# Pit_Crew.net
KiCad netlist of a schematic drawn in EAGLE
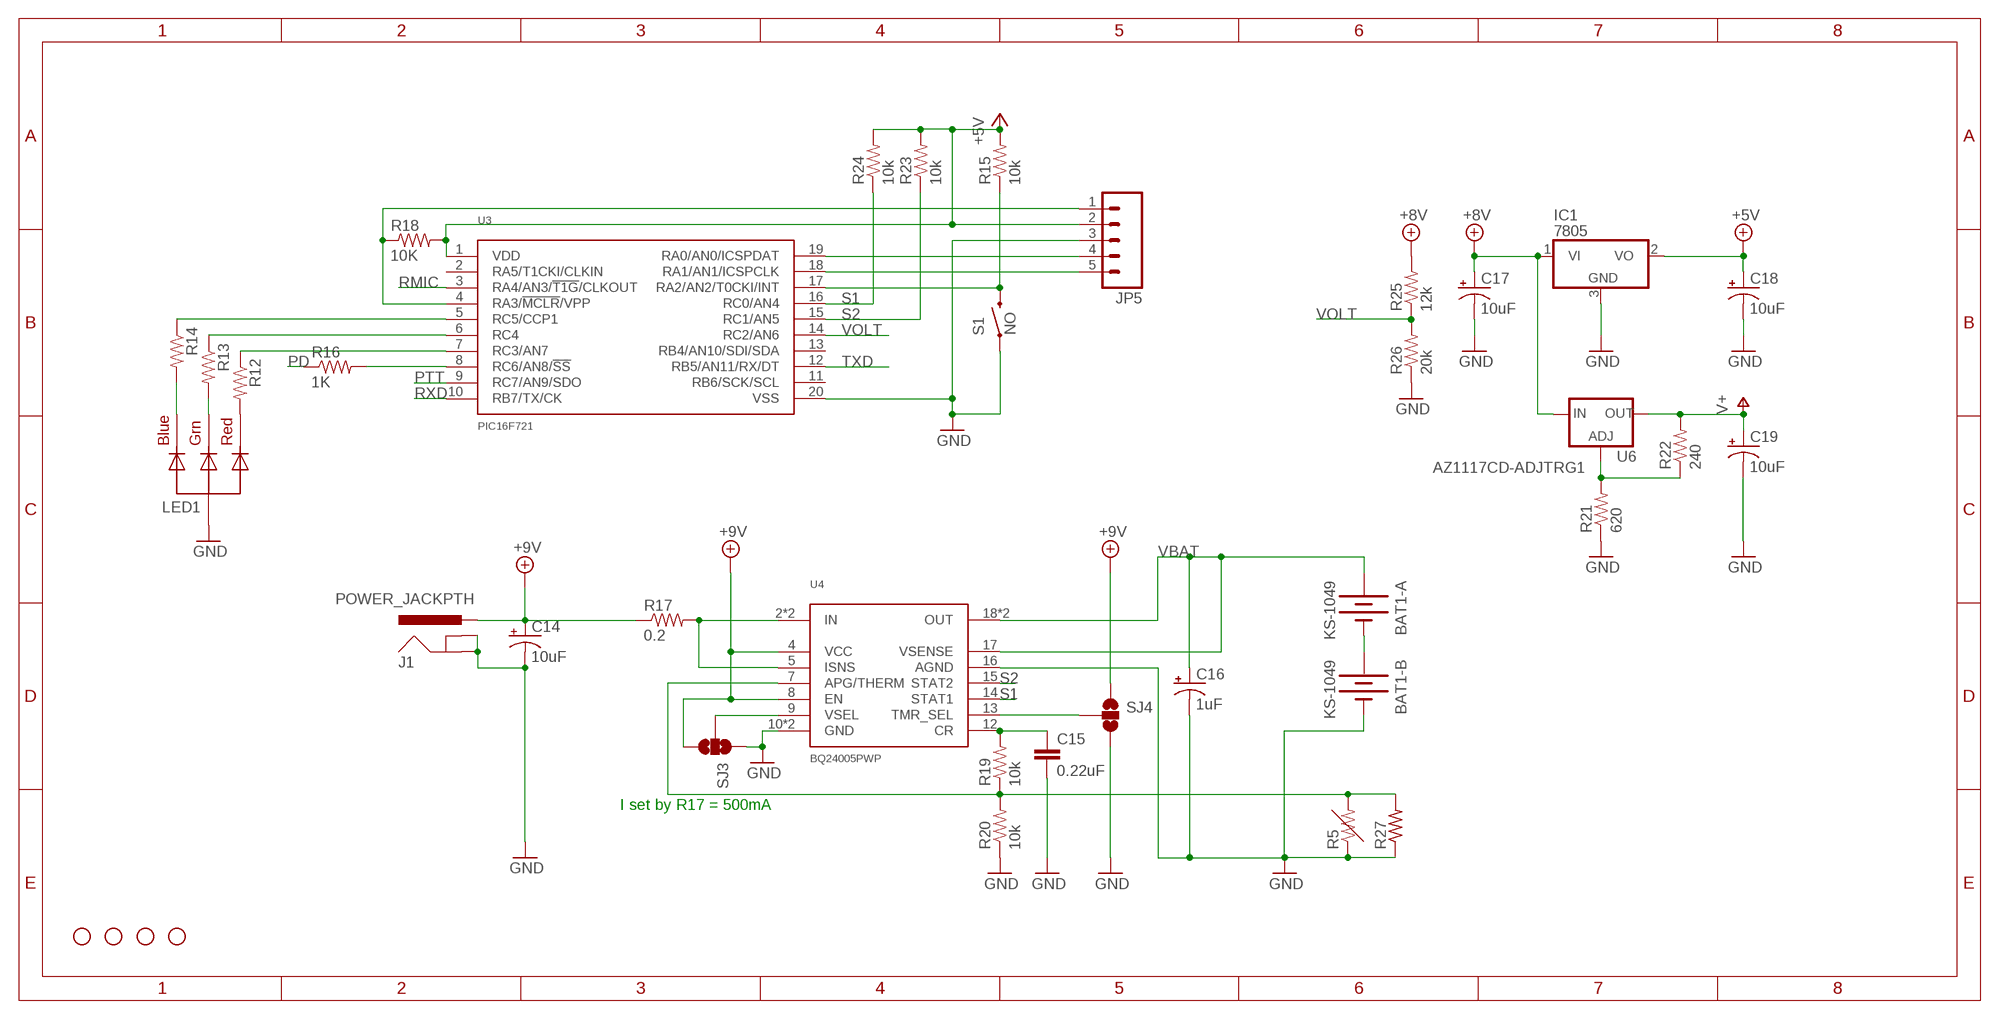
[diagram p0: schematic, sheet 1]
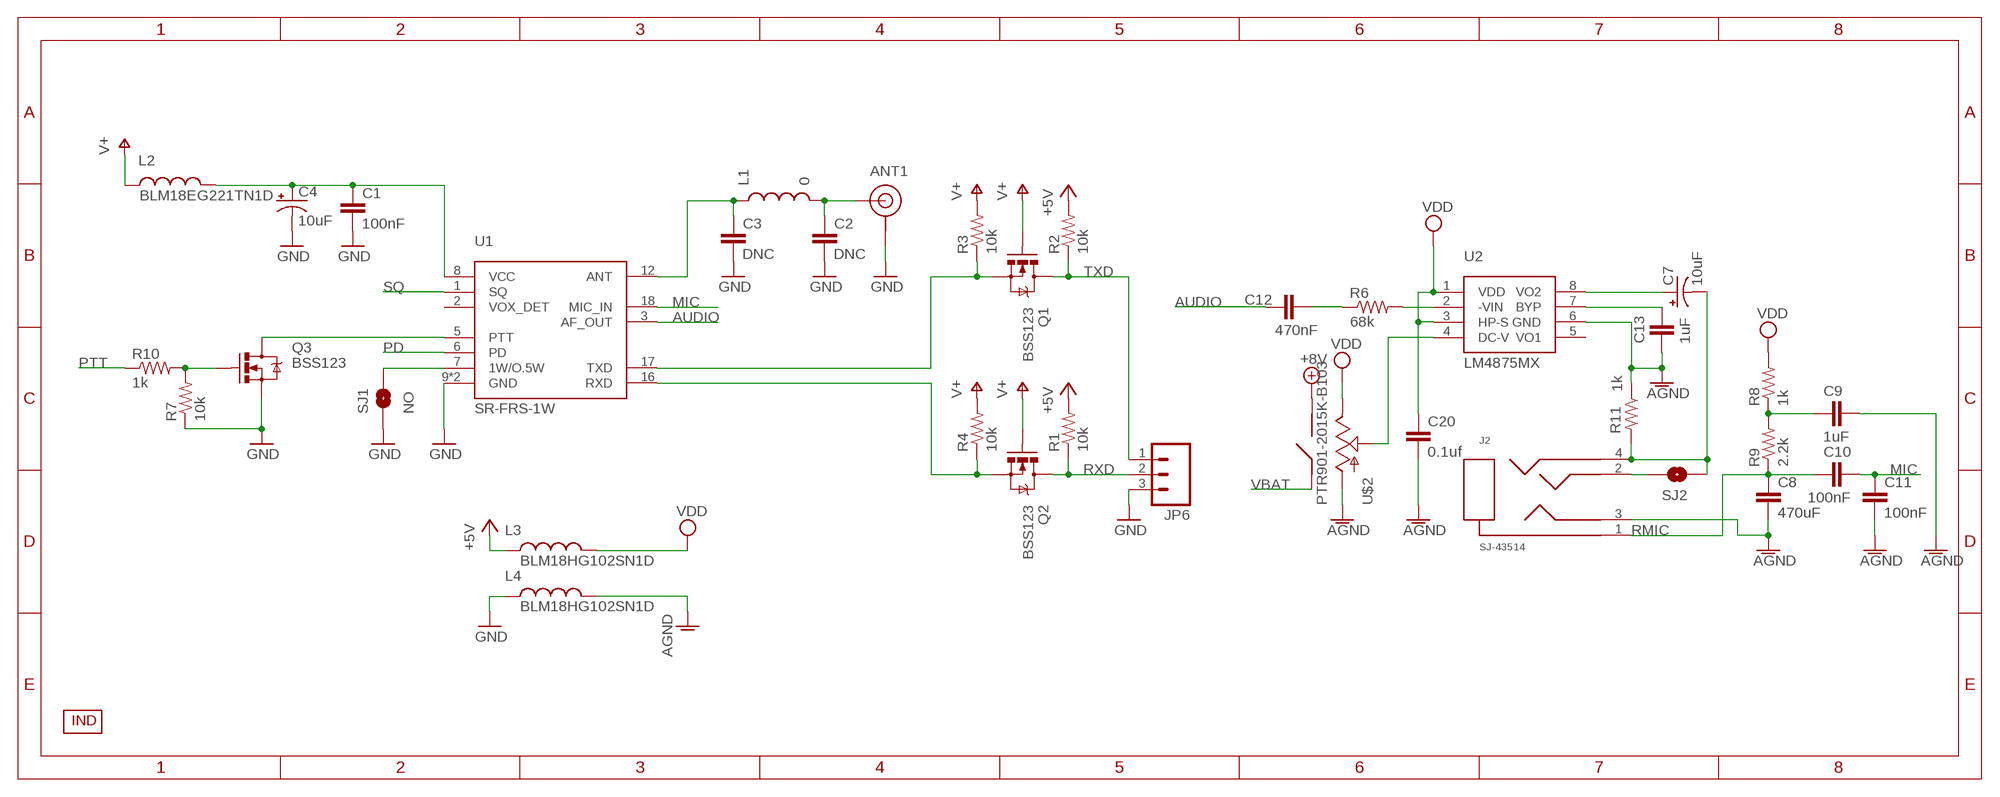
[diagram p1: schematic, sheet 2]

(export (version "E")
  (design (tool "Eeschema 10.0.6"))
  (components
    (comp (ref "ANT1")
      (value "SMA")
      (footprint "eagle-import:CONSMA002")
      (libsource (lib "eagle-import") (part "SMA"))
    )
    (comp (ref "C1")
      (value "100nF")
      (footprint "eagle-import:0805")
      (libsource (lib "eagle-import") (part "CAP0805"))
    )
    (comp (ref "C2")
      (value "DNC")
      (footprint "eagle-import:0805")
      (libsource (lib "eagle-import") (part "CAP0805"))
    )
    (comp (ref "C3")
      (value "DNC")
      (footprint "eagle-import:0805")
      (libsource (lib "eagle-import") (part "CAP0805"))
    )
    (comp (ref "C4")
      (value "10uF")
      (footprint "eagle-import:EIA3216")
      (libsource (lib "eagle-import") (part "CAP_POL1206"))
    )
    (comp (ref "C7")
      (value "10uF")
      (footprint "eagle-import:EIA3216")
      (libsource (lib "eagle-import") (part "10UF-TANT"))
    )
    (comp (ref "C8")
      (value "470uF")
      (footprint "eagle-import:0805")
      (libsource (lib "eagle-import") (part "CAP0805"))
    )
    (comp (ref "C9")
      (value "1uF")
      (footprint "eagle-import:0805")
      (libsource (lib "eagle-import") (part "CAP0805"))
    )
    (comp (ref "C10")
      (value "100nF")
      (footprint "eagle-import:0805")
      (libsource (lib "eagle-import") (part "CAP0805"))
    )
    (comp (ref "C11")
      (value "100nF")
      (footprint "eagle-import:0805")
      (libsource (lib "eagle-import") (part "CAP0805"))
    )
    (comp (ref "C12")
      (value "470nF")
      (footprint "eagle-import:0805")
      (libsource (lib "eagle-import") (part "CAP0805"))
    )
    (comp (ref "C13")
      (value "1uF")
      (footprint "eagle-import:0805")
      (libsource (lib "eagle-import") (part "CAP0805"))
    )
    (comp (ref "C20")
      (value "0.1uf")
      (footprint "eagle-import:0805")
      (libsource (lib "eagle-import") (part "CAP0805"))
    )
    (comp (ref "J2")
      (value "SJ-43514")
      (footprint "eagle-import:SJ-43514")
      (libsource (lib "eagle-import") (part "SJ-43514"))
    )
    (comp (ref "JP6")
      (value "M03LOCK")
      (footprint "eagle-import:1X03_LOCK")
      (libsource (lib "eagle-import") (part "M03LOCK"))
    )
    (comp (ref "L1")
      (value "0")
      (footprint "eagle-import:1007")
      (libsource (lib "eagle-import") (part "INDUCTOR1007"))
    )
    (comp (ref "L2")
      (value "BLM18EG221TN1D")
      (footprint "eagle-import:0603")
      (libsource (lib "eagle-import") (part "INDUCTOR0603"))
    )
    (comp (ref "L3")
      (value "BLM18HG102SN1D")
      (footprint "eagle-import:0603")
      (libsource (lib "eagle-import") (part "INDUCTOR0603"))
    )
    (comp (ref "L4")
      (value "BLM18HG102SN1D")
      (footprint "eagle-import:0603")
      (libsource (lib "eagle-import") (part "INDUCTOR0603"))
    )
    (comp (ref "Q1")
      (value "BSS123")
      (footprint "eagle-import:SOT23")
      (libsource (lib "eagle-import") (part "MOSFET-NCHANNELBSS123LT1G"))
    )
    (comp (ref "Q2")
      (value "BSS123")
      (footprint "eagle-import:SOT23")
      (libsource (lib "eagle-import") (part "MOSFET-NCHANNELBSS123LT1G"))
    )
    (comp (ref "Q3")
      (value "BSS123")
      (footprint "eagle-import:SOT23")
      (libsource (lib "eagle-import") (part "MOSFET-NCHANNELBSS123LT1G"))
    )
    (comp (ref "R1")
      (value "10k")
      (footprint "eagle-import:0805")
      (libsource (lib "eagle-import") (part "RESISTOR0805-RES"))
    )
    (comp (ref "R2")
      (value "10k")
      (footprint "eagle-import:0805")
      (libsource (lib "eagle-import") (part "RESISTOR0805-RES"))
    )
    (comp (ref "R3")
      (value "10k")
      (footprint "eagle-import:0805")
      (libsource (lib "eagle-import") (part "RESISTOR0805-RES"))
    )
    (comp (ref "R4")
      (value "10k")
      (footprint "eagle-import:0805")
      (libsource (lib "eagle-import") (part "RESISTOR0805-RES"))
    )
    (comp (ref "R6")
      (value "68k")
      (footprint "eagle-import:0805")
      (libsource (lib "eagle-import") (part "RESISTOR0805-RES"))
    )
    (comp (ref "R7")
      (value "10k")
      (footprint "eagle-import:0805")
      (libsource (lib "eagle-import") (part "RESISTOR0805-RES"))
    )
    (comp (ref "R8")
      (value "1k")
      (footprint "eagle-import:0805")
      (libsource (lib "eagle-import") (part "RESISTOR0805-RES"))
    )
    (comp (ref "R9")
      (value "2.2k")
      (footprint "eagle-import:0805")
      (libsource (lib "eagle-import") (part "RESISTOR0805-RES"))
    )
    (comp (ref "R10")
      (value "1k")
      (footprint "eagle-import:0805")
      (libsource (lib "eagle-import") (part "RESISTOR0805-RES"))
    )
    (comp (ref "R11")
      (value "1k")
      (footprint "eagle-import:0805")
      (libsource (lib "eagle-import") (part "RESISTOR0805-RES"))
    )
    (comp (ref "SJ1")
      (value "NO")
      (footprint "eagle-import:SJ_2S-NO")
      (libsource (lib "eagle-import") (part "SOLDERJUMPERNO"))
    )
    (comp (ref "SJ2")
      (value "SOLDERJUMPERNO")
      (footprint "eagle-import:SJ_2S-NO")
      (libsource (lib "eagle-import") (part "SOLDERJUMPERNO"))
    )
    (comp (ref "U$2")
      (value "PTR901-2015K-B103")
      (footprint "eagle-import:PTR901-2015K-B103")
      (libsource (lib "eagle-import") (part "PTR901-2015K-B103"))
    )
    (comp (ref "U$3")
      (value "INDPK1")
      (footprint "eagle-import:PICKIT-PIN-1")
      (libsource (lib "eagle-import") (part "INDPK1"))
    )
    (comp (ref "U1")
      (value "SR-FRS-1W")
      (footprint "eagle-import:SR-FRS-1W")
      (libsource (lib "eagle-import") (part "SR-FRS-1W"))
    )
    (comp (ref "U2")
      (value "LM4875MX")
      (footprint "eagle-import:SO-8")
      (libsource (lib "eagle-import") (part "LM4875MX"))
    )
    (comp (ref "BAT1")
      (value "KS-1049")
      (footprint "eagle-import:KEYSTONE_1049")
      (fields (field (name "PARTNO") "1049"))
      (libsource (lib "eagle-import") (part "BATTERY-2CELL"))
    )
    (comp (ref "C14")
      (value "10uF")
      (footprint "eagle-import:EIA3216")
      (libsource (lib "eagle-import") (part "10UF-TANT"))
    )
    (comp (ref "C15")
      (value "0.22uF")
      (footprint "eagle-import:0805")
      (libsource (lib "eagle-import") (part "CAP0805"))
    )
    (comp (ref "C16")
      (value "1uF")
      (footprint "eagle-import:EIA3216")
      (libsource (lib "eagle-import") (part "10UF-TANT"))
    )
    (comp (ref "C17")
      (value "10uF")
      (footprint "eagle-import:EIA3216")
      (libsource (lib "eagle-import") (part "10UF-TANT"))
    )
    (comp (ref "C18")
      (value "10uF")
      (footprint "eagle-import:EIA3216")
      (libsource (lib "eagle-import") (part "10UF-TANT"))
    )
    (comp (ref "C19")
      (value "10uF")
      (footprint "eagle-import:EIA3216")
      (libsource (lib "eagle-import") (part "10UF-TANT"))
    )
    (comp (ref "IC1")
      (value "7805")
      (footprint "eagle-import:TO252")
      (libsource (lib "eagle-import") (part "78DT06"))
    )
    (comp (ref "J1")
      (value "POWER_JACKPTH")
      (footprint "eagle-import:POWER_JACK_PTH")
      (libsource (lib "eagle-import") (part "POWER_JACKPTH"))
    )
    (comp (ref "JP5")
      (value "M05LOCK_LONGPADS")
      (footprint "eagle-import:1X05_LOCK_LONGPADS")
      (libsource (lib "eagle-import") (part "M05LOCK_LONGPADS"))
    )
    (comp (ref "LED1")
      (value "RGBLED_CA-5MM")
      (footprint "eagle-import:LED5MMRGB")
      (libsource (lib "eagle-import") (part "RGBLED_CA-5MM"))
    )
    (comp (ref "R5")
      (value "RESISTOR0805-RES")
      (footprint "eagle-import:0805")
      (libsource (lib "eagle-import") (part "RESISTOR0805-RES"))
    )
    (comp (ref "R12")
      (value "RESISTOR0805-RES")
      (footprint "eagle-import:0805")
      (libsource (lib "eagle-import") (part "RESISTOR0805-RES"))
    )
    (comp (ref "R13")
      (value "RESISTOR0805-RES")
      (footprint "eagle-import:0805")
      (libsource (lib "eagle-import") (part "RESISTOR0805-RES"))
    )
    (comp (ref "R14")
      (value "RESISTOR0805-RES")
      (footprint "eagle-import:0805")
      (libsource (lib "eagle-import") (part "RESISTOR0805-RES"))
    )
    (comp (ref "R15")
      (value "10k")
      (footprint "eagle-import:0805")
      (libsource (lib "eagle-import") (part "RESISTOR0805-RES"))
    )
    (comp (ref "R16")
      (value "1K")
      (footprint "eagle-import:0805")
      (fields (field (name "PARTNO") "RC0805FR-071KL"))
      (libsource (lib "eagle-import") (part "RES_1K_1%_0805"))
    )
    (comp (ref "R17")
      (value "0.2")
      (footprint "eagle-import:R2512")
      (libsource (lib "eagle-import") (part "RESISTOR2512"))
    )
    (comp (ref "R18")
      (value "10K")
      (footprint "eagle-import:0805")
      (fields (field (name "PARTNO") "RC0805FR-0710KL"))
      (libsource (lib "eagle-import") (part "RES_10K_1%_0805"))
    )
    (comp (ref "R19")
      (value "10k")
      (footprint "eagle-import:0805")
      (libsource (lib "eagle-import") (part "RESISTOR0805-RES"))
    )
    (comp (ref "R20")
      (value "10k")
      (footprint "eagle-import:0805")
      (libsource (lib "eagle-import") (part "RESISTOR0805-RES"))
    )
    (comp (ref "R21")
      (value "620")
      (footprint "eagle-import:0805")
      (libsource (lib "eagle-import") (part "RESISTOR0805-RES"))
    )
    (comp (ref "R22")
      (value "240")
      (footprint "eagle-import:0805")
      (libsource (lib "eagle-import") (part "RESISTOR0805-RES"))
    )
    (comp (ref "R23")
      (value "10k")
      (footprint "eagle-import:0805")
      (libsource (lib "eagle-import") (part "RESISTOR0805-RES"))
    )
    (comp (ref "R24")
      (value "10k")
      (footprint "eagle-import:0805")
      (libsource (lib "eagle-import") (part "RESISTOR0805-RES"))
    )
    (comp (ref "R25")
      (value "12k")
      (footprint "eagle-import:0805")
      (libsource (lib "eagle-import") (part "RESISTOR0805-RES"))
    )
    (comp (ref "R26")
      (value "20k")
      (footprint "eagle-import:0805")
      (libsource (lib "eagle-import") (part "RESISTOR0805-RES"))
    )
    (comp (ref "R27")
      (value "R-US_0207/7")
      (footprint "eagle-import:0207_7")
      (libsource (lib "eagle-import") (part "R-US_0207/7"))
    )
    (comp (ref "S1")
      (value "NO")
      (footprint "eagle-import:TACTILE-PTH-SIDEEZ")
      (libsource (lib "eagle-import") (part "SWITCH-MOMENTARY-2SIDE_EZ"))
    )
    (comp (ref "SJ3")
      (value "SOLDERJUMPER_2WAYS")
      (footprint "eagle-import:SJ_3")
      (libsource (lib "eagle-import") (part "SOLDERJUMPER_2WAYS"))
    )
    (comp (ref "SJ4")
      (value "SOLDERJUMPER_2WAYS")
      (footprint "eagle-import:SJ_3")
      (libsource (lib "eagle-import") (part "SOLDERJUMPER_2WAYS"))
    )
    (comp (ref "STANDOFF1")
      (value "STAND-OFF")
      (footprint "eagle-import:STAND-OFF")
      (libsource (lib "eagle-import") (part "STAND-OFF"))
    )
    (comp (ref "STANDOFF2")
      (value "STAND-OFF")
      (footprint "eagle-import:STAND-OFF")
      (libsource (lib "eagle-import") (part "STAND-OFF"))
    )
    (comp (ref "STANDOFF3")
      (value "STAND-OFF")
      (footprint "eagle-import:STAND-OFF")
      (libsource (lib "eagle-import") (part "STAND-OFF"))
    )
    (comp (ref "STANDOFF4")
      (value "STAND-OFF")
      (footprint "eagle-import:STAND-OFF")
      (libsource (lib "eagle-import") (part "STAND-OFF"))
    )
    (comp (ref "U3")
      (value "PIC16F721")
      (footprint "eagle-import:SSOP-20")
      (libsource (lib "eagle-import") (part "PIC16F721"))
    )
    (comp (ref "U4")
      (value "BQ24005PWP")
      (footprint "eagle-import:HTSSOP-20")
      (libsource (lib "eagle-import") (part "BQ24005PWP"))
    )
    (comp (ref "U6")
      (value "AZ1117CD-ADJTRG1")
      (footprint "eagle-import:V-REG_DPACK")
      (libsource (lib "eagle-import") (part "V_REG_317DPACK"))
    )
  )
  (nets
    (net (code "1") (name "+5V") (class "Default")
      (node (ref "C18") (pin "A") (pinfunction "+_A") (pintype "passive"))
      (node (ref "IC1") (pin "2") (pinfunction "VO_2") (pintype "passive"))
      (node (ref "JP5") (pin "2") (pinfunction "2_2") (pintype "passive"))
      (node (ref "L3") (pin "1") (pinfunction "1_1") (pintype "passive"))
      (node (ref "R1") (pin "2") (pinfunction "2_2") (pintype "passive"))
      (node (ref "R15") (pin "2") (pinfunction "2_2") (pintype "passive"))
      (node (ref "R18") (pin "2") (pinfunction "2_2") (pintype "passive"))
      (node (ref "R2") (pin "2") (pinfunction "2_2") (pintype "passive"))
      (node (ref "R23") (pin "2") (pinfunction "2_2") (pintype "passive"))
      (node (ref "R24") (pin "2") (pinfunction "2_2") (pintype "passive"))
      (node (ref "U3") (pin "1") (pinfunction "VDD_1") (pintype "bidirectional"))
    )
    (net (code "2") (name "+8V") (class "Default")
      (node (ref "C17") (pin "A") (pinfunction "+_A") (pintype "passive"))
      (node (ref "IC1") (pin "1") (pinfunction "VI_1") (pintype "input"))
      (node (ref "R25") (pin "2") (pinfunction "2_2") (pintype "passive"))
      (node (ref "U$2") (pin "S1") (pinfunction "S1_S1") (pintype "passive"))
      (node (ref "U6") (pin "3") (pinfunction "IN_3") (pintype "input"))
    )
    (net (code "3") (name "+9V") (class "Default")
      (node (ref "C14") (pin "A") (pinfunction "+_A") (pintype "passive"))
      (node (ref "J1") (pin "PWR") (pinfunction "PWR_PWR") (pintype "bidirectional"))
      (node (ref "R17") (pin "1") (pinfunction "1_1") (pintype "passive"))
      (node (ref "SJ3") (pin "3") (pinfunction "3_3") (pintype "passive"))
      (node (ref "SJ4") (pin "1") (pinfunction "1_1") (pintype "passive"))
      (node (ref "U4") (pin "4") (pinfunction "VCC_4") (pintype "bidirectional"))
      (node (ref "U4") (pin "8") (pinfunction "EN_8") (pintype "bidirectional"))
    )
    (net (code "4") (name "AGND") (class "Default")
      (node (ref "C11") (pin "2") (pinfunction "2_2") (pintype "passive"))
      (node (ref "C13") (pin "1") (pinfunction "1_1") (pintype "passive"))
      (node (ref "C20") (pin "2") (pinfunction "2_2") (pintype "passive"))
      (node (ref "C8") (pin "2") (pinfunction "2_2") (pintype "passive"))
      (node (ref "C9") (pin "2") (pinfunction "2_2") (pintype "passive"))
      (node (ref "J2") (pin "3") (pinfunction "3_3") (pintype "bidirectional"))
      (node (ref "L4") (pin "2") (pinfunction "2_2") (pintype "passive"))
      (node (ref "R11") (pin "1") (pinfunction "1_1") (pintype "passive"))
      (node (ref "U$2") (pin "1") (pinfunction "CCW_1") (pintype "passive"))
      (node (ref "U2") (pin "6") (pinfunction "GND_6") (pintype "bidirectional"))
    )
    (net (code "5") (name "AUDIO") (class "Default")
      (node (ref "C12") (pin "1") (pinfunction "1_1") (pintype "passive"))
      (node (ref "U1") (pin "3") (pinfunction "AF_OUT_3") (pintype "bidirectional"))
    )
    (net (code "6") (name "GND") (class "Default")
      (node (ref "ANT1") (pin "1") (pinfunction "GND_1") (pintype "bidirectional"))
      (node (ref "ANT1") (pin "2") (pinfunction "GND_2") (pintype "bidirectional"))
      (node (ref "ANT1") (pin "3") (pinfunction "GND_3") (pintype "bidirectional"))
      (node (ref "ANT1") (pin "4") (pinfunction "GND_4") (pintype "bidirectional"))
      (node (ref "BAT1") (pin "B2-") (pinfunction "-_B2-") (pintype "power_in"))
      (node (ref "C1") (pin "2") (pinfunction "2_2") (pintype "passive"))
      (node (ref "C14") (pin "C") (pinfunction "-_C") (pintype "passive"))
      (node (ref "C15") (pin "2") (pinfunction "2_2") (pintype "passive"))
      (node (ref "C16") (pin "C") (pinfunction "-_C") (pintype "passive"))
      (node (ref "C17") (pin "C") (pinfunction "-_C") (pintype "passive"))
      (node (ref "C18") (pin "C") (pinfunction "-_C") (pintype "passive"))
      (node (ref "C19") (pin "C") (pinfunction "-_C") (pintype "passive"))
      (node (ref "C2") (pin "2") (pinfunction "2_2") (pintype "passive"))
      (node (ref "C3") (pin "2") (pinfunction "2_2") (pintype "passive"))
      (node (ref "C4") (pin "C") (pinfunction "-_C") (pintype "passive"))
      (node (ref "IC1") (pin "3") (pinfunction "GND_3") (pintype "passive"))
      (node (ref "J1") (pin "GND") (pinfunction "GND_GND") (pintype "bidirectional"))
      (node (ref "J1") (pin "GNDBREAK") (pinfunction "GNDBREAK_GNDBREAK") (pintype "bidirectional"))
      (node (ref "JP5") (pin "3") (pinfunction "3_3") (pintype "passive"))
      (node (ref "JP6") (pin "3") (pinfunction "3_3") (pintype "passive"))
      (node (ref "L4") (pin "1") (pinfunction "1_1") (pintype "passive"))
      (node (ref "LED1") (pin "2") (pinfunction "VCC_2") (pintype "bidirectional"))
      (node (ref "Q3") (pin "2") (pinfunction "S_2") (pintype "passive"))
      (node (ref "R20") (pin "1") (pinfunction "1_1") (pintype "passive"))
      (node (ref "R21") (pin "1") (pinfunction "1_1") (pintype "passive"))
      (node (ref "R26") (pin "1") (pinfunction "1_1") (pintype "passive"))
      (node (ref "R27") (pin "1") (pinfunction "1_1") (pintype "passive"))
      (node (ref "R5") (pin "1") (pinfunction "1_1") (pintype "passive"))
      (node (ref "R7") (pin "1") (pinfunction "1_1") (pintype "passive"))
      (node (ref "S1") (pin "1") (pinfunction "1_1") (pintype "passive"))
      (node (ref "SJ1") (pin "1") (pinfunction "1_1") (pintype "passive"))
      (node (ref "SJ3") (pin "1") (pinfunction "1_1") (pintype "passive"))
      (node (ref "SJ4") (pin "3") (pinfunction "3_3") (pintype "passive"))
      (node (ref "U1") (pin "10") (pinfunction "GND_10") (pintype "bidirectional"))
      (node (ref "U1") (pin "9") (pinfunction "GND_9") (pintype "bidirectional"))
      (node (ref "U3") (pin "20") (pinfunction "VSS_20") (pintype "bidirectional"))
      (node (ref "U4") (pin "10") (pinfunction "GND_10") (pintype "bidirectional"))
      (node (ref "U4") (pin "16") (pinfunction "AGND_16") (pintype "bidirectional"))
      (node (ref "U4") (pin "EP") (pinfunction "GND_EP") (pintype "bidirectional"))
    )
    (net (code "7") (name "MIC") (class "Default")
      (node (ref "C10") (pin "2") (pinfunction "2_2") (pintype "passive"))
      (node (ref "C11") (pin "1") (pinfunction "1_1") (pintype "passive"))
      (node (ref "U1") (pin "18") (pinfunction "MIC_IN_18") (pintype "bidirectional"))
    )
    (net (code "8") (name "Net-(ANT1-SIGNAL)") (class "Default")
      (node (ref "ANT1") (pin "C") (pinfunction "SIGNAL_C") (pintype "bidirectional"))
      (node (ref "C2") (pin "1") (pinfunction "1_1") (pintype "passive"))
      (node (ref "L1") (pin "2") (pinfunction "2_2") (pintype "passive"))
    )
    (net (code "9") (name "Net-(BAT1A--)") (class "Default")
      (node (ref "BAT1") (pin "B1-") (pinfunction "-_B1-") (pintype "power_in"))
      (node (ref "BAT1") (pin "B2+") (pinfunction "+_B2+") (pintype "power_in"))
    )
    (net (code "10") (name "Net-(C4-+)") (class "Default")
      (node (ref "C1") (pin "1") (pinfunction "1_1") (pintype "passive"))
      (node (ref "C4") (pin "A") (pinfunction "+_A") (pintype "passive"))
      (node (ref "L2") (pin "2") (pinfunction "2_2") (pintype "passive"))
      (node (ref "U1") (pin "8") (pinfunction "VCC_8") (pintype "bidirectional"))
    )
    (net (code "11") (name "Net-(C7-+)") (class "Default")
      (node (ref "C7") (pin "A") (pinfunction "+_A") (pintype "passive"))
      (node (ref "U2") (pin "8") (pinfunction "VO2_8") (pintype "bidirectional"))
    )
    (net (code "12") (name "Net-(C7--)") (class "Default")
      (node (ref "C7") (pin "C") (pinfunction "-_C") (pintype "passive"))
      (node (ref "J2") (pin "4") (pinfunction "4_4") (pintype "bidirectional"))
      (node (ref "R11") (pin "2") (pinfunction "2_2") (pintype "passive"))
      (node (ref "SJ2") (pin "2") (pinfunction "2_2") (pintype "passive"))
    )
    (net (code "13") (name "Net-(C9-Pad1)") (class "Default")
      (node (ref "C9") (pin "1") (pinfunction "1_1") (pintype "passive"))
      (node (ref "R8") (pin "1") (pinfunction "1_1") (pintype "passive"))
      (node (ref "R9") (pin "2") (pinfunction "2_2") (pintype "passive"))
    )
    (net (code "14") (name "Net-(C12-Pad2)") (class "Default")
      (node (ref "C12") (pin "2") (pinfunction "2_2") (pintype "passive"))
      (node (ref "R6") (pin "1") (pinfunction "1_1") (pintype "passive"))
    )
    (net (code "15") (name "Net-(J2-Pad2)") (class "Default")
      (node (ref "J2") (pin "2") (pinfunction "2_2") (pintype "bidirectional"))
      (node (ref "SJ2") (pin "1") (pinfunction "1_1") (pintype "passive"))
    )
    (net (code "16") (name "Net-(LED1-BLUE)") (class "Default")
      (node (ref "LED1") (pin "4") (pinfunction "BLUE_4") (pintype "bidirectional"))
      (node (ref "R14") (pin "2") (pinfunction "2_2") (pintype "passive"))
    )
    (net (code "17") (name "Net-(LED1-GREEN)") (class "Default")
      (node (ref "LED1") (pin "3") (pinfunction "GREEN_3") (pintype "bidirectional"))
      (node (ref "R13") (pin "2") (pinfunction "2_2") (pintype "passive"))
    )
    (net (code "18") (name "Net-(LED1-RED)") (class "Default")
      (node (ref "LED1") (pin "1") (pinfunction "RED_1") (pintype "bidirectional"))
      (node (ref "R12") (pin "2") (pinfunction "2_2") (pintype "passive"))
    )
    (net (code "19") (name "Net-(Q1-S)") (class "Default")
      (node (ref "Q1") (pin "2") (pinfunction "S_2") (pintype "passive"))
      (node (ref "R3") (pin "1") (pinfunction "1_1") (pintype "passive"))
      (node (ref "U1") (pin "17") (pinfunction "TXD_17") (pintype "bidirectional"))
    )
    (net (code "20") (name "Net-(Q2-S)") (class "Default")
      (node (ref "Q2") (pin "2") (pinfunction "S_2") (pintype "passive"))
      (node (ref "R4") (pin "1") (pinfunction "1_1") (pintype "passive"))
      (node (ref "U1") (pin "16") (pinfunction "RXD_16") (pintype "bidirectional"))
    )
    (net (code "21") (name "Net-(Q3-D)") (class "Default")
      (node (ref "Q3") (pin "3") (pinfunction "D_3") (pintype "passive"))
      (node (ref "U1") (pin "5") (pinfunction "PTT_5") (pintype "bidirectional"))
    )
    (net (code "22") (name "Net-(Q3-G)") (class "Default")
      (node (ref "Q3") (pin "1") (pinfunction "G_1") (pintype "passive"))
      (node (ref "R10") (pin "2") (pinfunction "2_2") (pintype "passive"))
      (node (ref "R7") (pin "2") (pinfunction "2_2") (pintype "passive"))
    )
    (net (code "23") (name "Net-(U$2-W)") (class "Default")
      (node (ref "U$2") (pin "2") (pinfunction "W_2") (pintype "passive"))
      (node (ref "U2") (pin "4") (pinfunction "DC-V_4") (pintype "bidirectional"))
    )
    (net (code "24") (name "Net-(U1-1W{slash}O.5W)") (class "Default")
      (node (ref "SJ1") (pin "2") (pinfunction "2_2") (pintype "passive"))
      (node (ref "U1") (pin "7") (pinfunction "1W/O.5W_7") (pintype "bidirectional"))
    )
    (net (code "25") (name "Net-(U1-ANT)") (class "Default")
      (node (ref "C3") (pin "1") (pinfunction "1_1") (pintype "passive"))
      (node (ref "L1") (pin "1") (pinfunction "1_1") (pintype "passive"))
      (node (ref "U1") (pin "12") (pinfunction "ANT_12") (pintype "bidirectional"))
    )
    (net (code "26") (name "Net-(U2--VIN)") (class "Default")
      (node (ref "R6") (pin "2") (pinfunction "2_2") (pintype "passive"))
      (node (ref "U2") (pin "2") (pinfunction "-VIN_2") (pintype "bidirectional"))
    )
    (net (code "27") (name "Net-(U2-BYP)") (class "Default")
      (node (ref "C13") (pin "2") (pinfunction "2_2") (pintype "passive"))
      (node (ref "U2") (pin "7") (pinfunction "BYP_7") (pintype "bidirectional"))
    )
    (net (code "28") (name "Net-(U3-RA0{slash}AN0{slash}ICSPDAT)") (class "Default")
      (node (ref "JP5") (pin "4") (pinfunction "4_4") (pintype "passive"))
      (node (ref "U3") (pin "19") (pinfunction "RA0/AN0/ICSPDAT_19") (pintype "bidirectional"))
    )
    (net (code "29") (name "Net-(U3-RA1{slash}AN1{slash}ICSPCLK)") (class "Default")
      (node (ref "JP5") (pin "5") (pinfunction "5_5") (pintype "passive"))
      (node (ref "U3") (pin "18") (pinfunction "RA1/AN1/ICSPCLK_18") (pintype "bidirectional"))
    )
    (net (code "30") (name "Net-(U3-RA2{slash}AN2{slash}T0CKI{slash}INT)") (class "Default")
      (node (ref "R15") (pin "1") (pinfunction "1_1") (pintype "passive"))
      (node (ref "S1") (pin "2") (pinfunction "2_2") (pintype "passive"))
      (node (ref "U3") (pin "17") (pinfunction "RA2/AN2/T0CKI/INT_17") (pintype "bidirectional"))
    )
    (net (code "31") (name "Net-(U3-RA3{slash}~{MCLR}{slash}VPP)") (class "Default")
      (node (ref "JP5") (pin "1") (pinfunction "1_1") (pintype "passive"))
      (node (ref "R18") (pin "1") (pinfunction "1_1") (pintype "passive"))
      (node (ref "U3") (pin "4") (pinfunction "RA3/~{MCLR}/VPP_4") (pintype "bidirectional"))
    )
    (net (code "32") (name "Net-(U3-RC3{slash}AN7)") (class "Default")
      (node (ref "R12") (pin "1") (pinfunction "1_1") (pintype "passive"))
      (node (ref "U3") (pin "7") (pinfunction "RC3/AN7_7") (pintype "bidirectional"))
    )
    (net (code "33") (name "Net-(U3-RC4)") (class "Default")
      (node (ref "R13") (pin "1") (pinfunction "1_1") (pintype "passive"))
      (node (ref "U3") (pin "6") (pinfunction "RC4_6") (pintype "bidirectional"))
    )
    (net (code "34") (name "Net-(U3-RC5{slash}CCP1)") (class "Default")
      (node (ref "R14") (pin "1") (pinfunction "1_1") (pintype "passive"))
      (node (ref "U3") (pin "5") (pinfunction "RC5/CCP1_5") (pintype "bidirectional"))
    )
    (net (code "35") (name "Net-(U3-RC6{slash}AN8{slash}~{SS})") (class "Default")
      (node (ref "R16") (pin "2") (pinfunction "2_2") (pintype "passive"))
      (node (ref "U3") (pin "8") (pinfunction "RC6/AN8/~{SS}_8") (pintype "bidirectional"))
    )
    (net (code "36") (name "Net-(U4-APG{slash}THERM)") (class "Default")
      (node (ref "R19") (pin "1") (pinfunction "1_1") (pintype "passive"))
      (node (ref "R20") (pin "2") (pinfunction "2_2") (pintype "passive"))
      (node (ref "R27") (pin "2") (pinfunction "2_2") (pintype "passive"))
      (node (ref "R5") (pin "2") (pinfunction "2_2") (pintype "passive"))
      (node (ref "U4") (pin "7") (pinfunction "APG/THERM_7") (pintype "bidirectional"))
    )
    (net (code "37") (name "Net-(U4-CR)") (class "Default")
      (node (ref "C15") (pin "1") (pinfunction "1_1") (pintype "passive"))
      (node (ref "R19") (pin "2") (pinfunction "2_2") (pintype "passive"))
      (node (ref "U4") (pin "12") (pinfunction "CR_12") (pintype "bidirectional"))
    )
    (net (code "38") (name "Net-(U4-ISNS)") (class "Default")
      (node (ref "R17") (pin "2") (pinfunction "2_2") (pintype "passive"))
      (node (ref "U4") (pin "2") (pinfunction "IN_2") (pintype "bidirectional"))
      (node (ref "U4") (pin "3") (pinfunction "IN_3") (pintype "bidirectional"))
      (node (ref "U4") (pin "5") (pinfunction "ISNS_5") (pintype "bidirectional"))
    )
    (net (code "39") (name "Net-(U4-TMR_SEL)") (class "Default")
      (node (ref "SJ4") (pin "2") (pinfunction "2_2") (pintype "passive"))
      (node (ref "U4") (pin "13") (pinfunction "TMR_SEL_13") (pintype "bidirectional"))
    )
    (net (code "40") (name "Net-(U4-VSEL)") (class "Default")
      (node (ref "SJ3") (pin "2") (pinfunction "2_2") (pintype "passive"))
      (node (ref "U4") (pin "9") (pinfunction "VSEL_9") (pintype "bidirectional"))
    )
    (net (code "41") (name "Net-(U6-ADJ)") (class "Default")
      (node (ref "R21") (pin "2") (pinfunction "2_2") (pintype "passive"))
      (node (ref "R22") (pin "1") (pinfunction "1_1") (pintype "passive"))
      (node (ref "U6") (pin "1") (pinfunction "ADJ_1") (pintype "input"))
    )
    (net (code "42") (name "PD") (class "Default")
      (node (ref "R16") (pin "1") (pinfunction "1_1") (pintype "passive"))
      (node (ref "U1") (pin "6") (pinfunction "PD_6") (pintype "bidirectional"))
    )
    (net (code "43") (name "PTT") (class "Default")
      (node (ref "R10") (pin "1") (pinfunction "1_1") (pintype "passive"))
      (node (ref "U3") (pin "9") (pinfunction "RC7/AN9/SDO_9") (pintype "bidirectional"))
    )
    (net (code "44") (name "RMIC") (class "Default")
      (node (ref "C10") (pin "1") (pinfunction "1_1") (pintype "passive"))
      (node (ref "C8") (pin "1") (pinfunction "1_1") (pintype "passive"))
      (node (ref "J2") (pin "1") (pinfunction "1_1") (pintype "bidirectional"))
      (node (ref "R9") (pin "1") (pinfunction "1_1") (pintype "passive"))
      (node (ref "U3") (pin "3") (pinfunction "RA4/AN3/~{T1G}/CLKOUT_3") (pintype "bidirectional"))
    )
    (net (code "45") (name "RXD") (class "Default")
      (node (ref "JP6") (pin "2") (pinfunction "2_2") (pintype "passive"))
      (node (ref "Q2") (pin "3") (pinfunction "D_3") (pintype "passive"))
      (node (ref "R1") (pin "1") (pinfunction "1_1") (pintype "passive"))
      (node (ref "U3") (pin "10") (pinfunction "RB7/TX/CK_10") (pintype "bidirectional"))
    )
    (net (code "46") (name "S1") (class "Default")
      (node (ref "R24") (pin "1") (pinfunction "1_1") (pintype "passive"))
      (node (ref "U3") (pin "16") (pinfunction "RC0/AN4_16") (pintype "bidirectional"))
      (node (ref "U4") (pin "14") (pinfunction "STAT1_14") (pintype "bidirectional"))
    )
    (net (code "47") (name "S2") (class "Default")
      (node (ref "R23") (pin "1") (pinfunction "1_1") (pintype "passive"))
      (node (ref "U3") (pin "15") (pinfunction "RC1/AN5_15") (pintype "bidirectional"))
      (node (ref "U4") (pin "15") (pinfunction "STAT2_15") (pintype "bidirectional"))
    )
    (net (code "48") (name "SQ") (class "Default")
      (node (ref "U1") (pin "1") (pinfunction "SQ_1") (pintype "bidirectional"))
    )
    (net (code "49") (name "TXD") (class "Default")
      (node (ref "JP6") (pin "1") (pinfunction "1_1") (pintype "passive"))
      (node (ref "Q1") (pin "3") (pinfunction "D_3") (pintype "passive"))
      (node (ref "R2") (pin "1") (pinfunction "1_1") (pintype "passive"))
      (node (ref "U3") (pin "12") (pinfunction "RB5/AN11/RX/DT_12") (pintype "bidirectional"))
    )
    (net (code "50") (name "V+") (class "Default")
      (node (ref "C19") (pin "A") (pinfunction "+_A") (pintype "passive"))
      (node (ref "L2") (pin "1") (pinfunction "1_1") (pintype "passive"))
      (node (ref "Q1") (pin "1") (pinfunction "G_1") (pintype "passive"))
      (node (ref "Q2") (pin "1") (pinfunction "G_1") (pintype "passive"))
      (node (ref "R22") (pin "2") (pinfunction "2_2") (pintype "passive"))
      (node (ref "R3") (pin "2") (pinfunction "2_2") (pintype "passive"))
      (node (ref "R4") (pin "2") (pinfunction "2_2") (pintype "passive"))
      (node (ref "U6") (pin "4") (pinfunction "OUT_4") (pintype "output"))
    )
    (net (code "51") (name "VBAT") (class "Default")
      (node (ref "BAT1") (pin "B1+") (pinfunction "+_B1+") (pintype "power_in"))
      (node (ref "C16") (pin "A") (pinfunction "+_A") (pintype "passive"))
      (node (ref "U$2") (pin "S2") (pinfunction "S2_S2") (pintype "passive"))
      (node (ref "U4") (pin "17") (pinfunction "VSENSE_17") (pintype "bidirectional"))
      (node (ref "U4") (pin "18") (pinfunction "OUT_18") (pintype "bidirectional"))
      (node (ref "U4") (pin "19") (pinfunction "OUT_19") (pintype "bidirectional"))
    )
    (net (code "52") (name "VDD") (class "Default")
      (node (ref "C20") (pin "1") (pinfunction "1_1") (pintype "passive"))
      (node (ref "L3") (pin "2") (pinfunction "2_2") (pintype "passive"))
      (node (ref "R8") (pin "2") (pinfunction "2_2") (pintype "passive"))
      (node (ref "U$2") (pin "3") (pinfunction "CW_3") (pintype "passive"))
      (node (ref "U2") (pin "1") (pinfunction "VDD_1") (pintype "bidirectional"))
      (node (ref "U2") (pin "3") (pinfunction "HP-S_3") (pintype "bidirectional"))
    )
    (net (code "53") (name "VOLT") (class "Default")
      (node (ref "R25") (pin "1") (pinfunction "1_1") (pintype "passive"))
      (node (ref "R26") (pin "2") (pinfunction "2_2") (pintype "passive"))
      (node (ref "U3") (pin "14") (pinfunction "RC2/AN6_14") (pintype "bidirectional"))
    )
    (net (code "54") (name "unconnected-(U1-VOX_DET-Pad2)") (class "Default")
      (node (ref "U1") (pin "2") (pinfunction "VOX_DET_2") (pintype "bidirectional"))
    )
    (net (code "55") (name "unconnected-(U2-VO1-Pad5)") (class "Default")
      (node (ref "U2") (pin "5") (pinfunction "VO1_5") (pintype "bidirectional"))
    )
    (net (code "56") (name "unconnected-(U3-RA5{slash}T1CKI{slash}CLKIN-Pad2)") (class "Default")
      (node (ref "U3") (pin "2") (pinfunction "RA5/T1CKI/CLKIN_2") (pintype "bidirectional"))
    )
    (net (code "57") (name "unconnected-(U3-RB4{slash}AN10{slash}SDI{slash}SDA-Pad13)") (class "Default")
      (node (ref "U3") (pin "13") (pinfunction "RB4/AN10/SDI/SDA_13") (pintype "bidirectional"))
    )
    (net (code "58") (name "unconnected-(U3-RB6{slash}SCK{slash}SCL-Pad11)") (class "Default")
      (node (ref "U3") (pin "11") (pinfunction "RB6/SCK/SCL_11") (pintype "bidirectional"))
    )
  )
)
